# POWR001_BCR__LT3652.net
KiCad netlist of a schematic drawn in Altium Designer
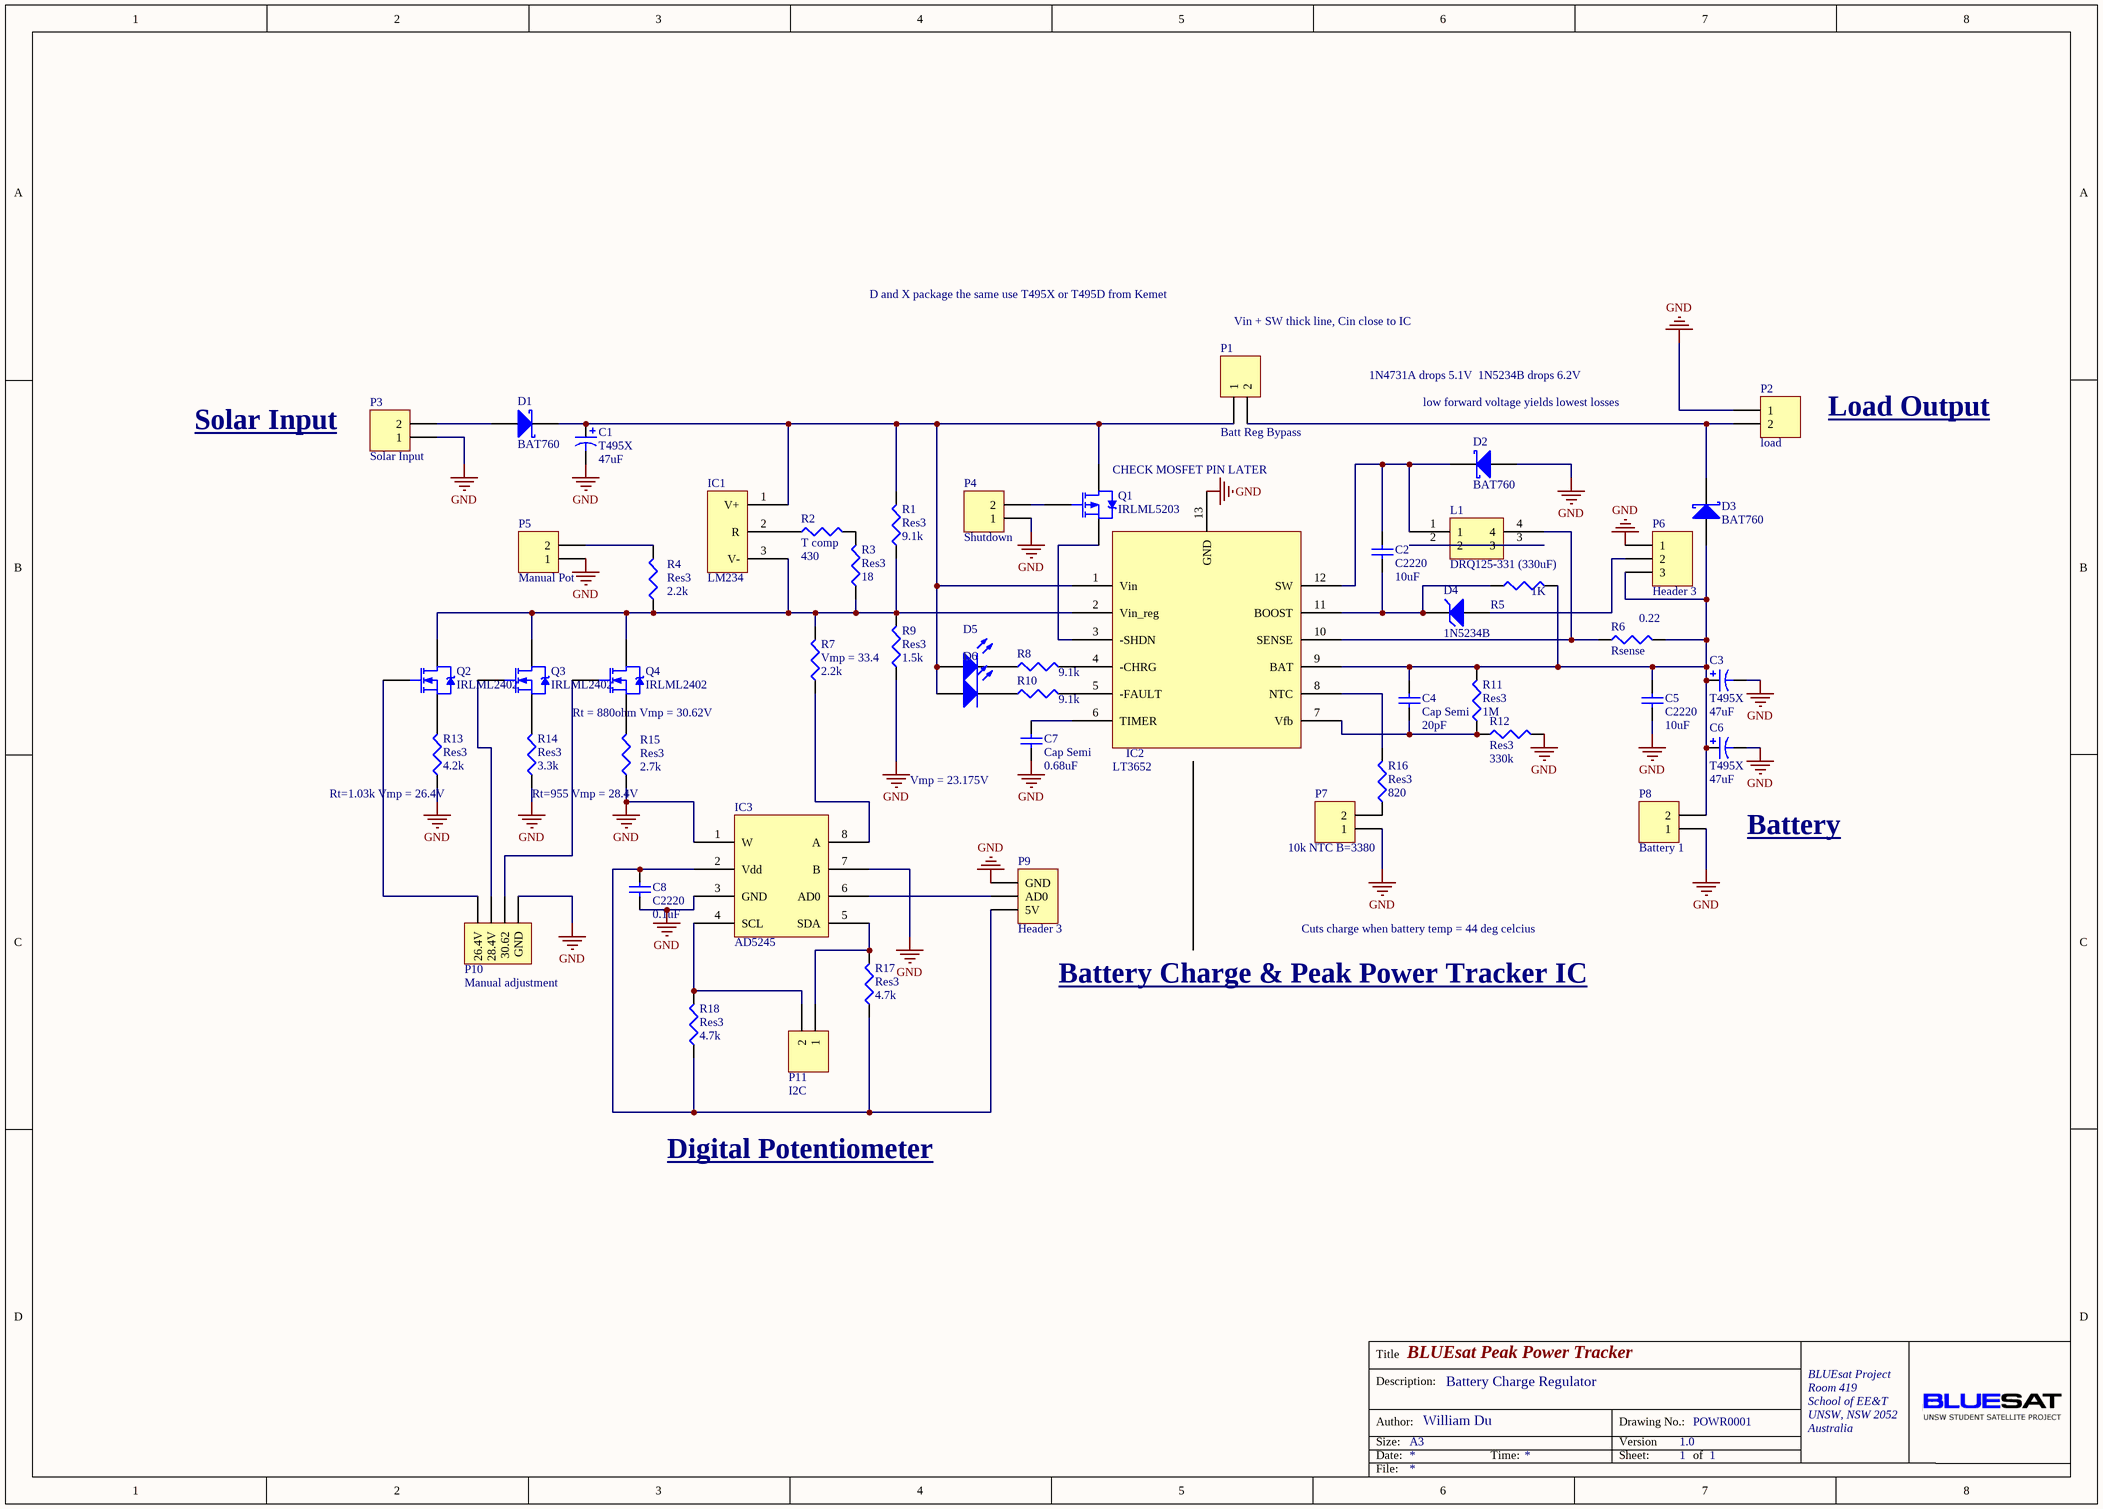
[diagram p0: POWR001_BCR_ LT3652.SchDoc]

(export (version "E")
  (design (tool "Eeschema 10.0.6"))
  (components
    (comp (ref "C1")
      (value "T495X")
      (footprint "X")
      (description "Solid Tantalum Chip Capacitor, Standard T495 Series - Low ESR, Surge Robust")
      (fields (field (name "ALTIUM_VALUE") "47uF") (field (name "PUBLISHER") "Altium Limited"))
      (libsource (lib "KEMET Chip Capacitor") (part "T495X"))
    )
    (comp (ref "C2")
      (value "C2220")
      (footprint "2220")
      (description "Ceramic Chip Capacitor - Standard")
      (fields (field (name "ALTIUM_VALUE") "10uF") (field (name "PUBLISHER") "Altium Limited"))
      (libsource (lib "KEMET Chip Capacitor") (part "C2220"))
    )
    (comp (ref "C3")
      (value "T495X")
      (footprint "X")
      (description "Solid Tantalum Chip Capacitor, Standard T495 Series - Low ESR, Surge Robust")
      (fields (field (name "ALTIUM_VALUE") "47uF") (field (name "PUBLISHER") "Altium Limited"))
      (libsource (lib "KEMET Chip Capacitor") (part "T495X"))
    )
    (comp (ref "C4")
      (value "Cap Semi")
      (footprint "CAPC3216L")
      (description "Capacitor (Semiconductor SIM Model)")
      (fields (field (name "ALTIUM_VALUE") "20pF") (field (name "PUBLISHER") "Altium Limited"))
      (libsource (lib "Miscellaneous Devices") (part "Cap Semi"))
    )
    (comp (ref "C5")
      (value "C2220")
      (footprint "2220")
      (description "Ceramic Chip Capacitor - Standard")
      (fields (field (name "ALTIUM_VALUE") "10uF") (field (name "PUBLISHER") "Altium Limited"))
      (libsource (lib "KEMET Chip Capacitor") (part "C2220"))
    )
    (comp (ref "C6")
      (value "T495X")
      (footprint "X")
      (description "Solid Tantalum Chip Capacitor, Standard T495 Series - Low ESR, Surge Robust")
      (fields (field (name "ALTIUM_VALUE") "47uF") (field (name "PUBLISHER") "Altium Limited"))
      (libsource (lib "KEMET Chip Capacitor") (part "T495X"))
    )
    (comp (ref "C7")
      (value "Cap Semi")
      (footprint "CAPC3216L")
      (description "Capacitor (Semiconductor SIM Model)")
      (fields (field (name "ALTIUM_VALUE") "0.68uF") (field (name "PUBLISHER") "Altium Limited"))
      (libsource (lib "Miscellaneous Devices") (part "Cap Semi"))
    )
    (comp (ref "C8")
      (value "C2220")
      (footprint "KEMET Electronics Footprints:2220")
      (description "Ceramic Chip Capacitor - Standard")
      (fields (field (name "ALTIUM_VALUE") "0.1uF") (field (name "PUBLISHER") "Altium Limited"))
      (libsource (lib "KEMET Chip Capacitor") (part "C2220"))
    )
    (comp (ref "D1")
      (value "BAT760")
      (footprint "SOD323")
      (description "Schottky Diode")
      (fields (field (name "PUBLISHER") "Altium Limited"))
      (libsource (lib "Miscellaneous Devices") (part "D Schottky"))
    )
    (comp (ref "D2")
      (value "BAT760")
      (footprint "LT3652:SOD323")
      (description "Schottky Diode")
      (fields (field (name "PUBLISHER") "Altium Limited"))
      (libsource (lib "Miscellaneous Devices") (part "D Schottky"))
    )
    (comp (ref "D3")
      (value "BAT760")
      (footprint "LT3652:SOD323")
      (description "Schottky Diode")
      (fields (field (name "PUBLISHER") "Altium Limited"))
      (libsource (lib "Miscellaneous Devices") (part "D Schottky"))
    )
    (comp (ref "D4")
      (value "1N5234B")
      (footprint "DO-35")
      (description "Half Watt Zener")
      (fields (field (name "PUBLISHER") "Altium Limited"))
      (libsource (lib "FSC Discrete Diode") (part "1N5234B"))
    )
    (comp (ref "D5")
      (value "~")
      (footprint "DSO-C2/D5.6")
      (description "Typical BLUE SiC LED")
      (fields (field (name "PUBLISHER") "Altium Limited"))
      (libsource (lib "Miscellaneous Devices") (part "LED3"))
    )
    (comp (ref "D6")
      (value "~")
      (footprint "DSO-C2/D5.6")
      (description "Typical BLUE SiC LED")
      (fields (field (name "PUBLISHER") "Altium Limited"))
      (libsource (lib "Miscellaneous Devices") (part "LED3"))
    )
    (comp (ref "IC1")
      (value "LM234")
      (footprint "Miscellaneous Connectors:HDR1X3")
      (libsource (lib "LT3652") (part "LM234"))
    )
    (comp (ref "IC2") (value "LT3652") (footprint "MSOP12") (libsource (lib "LT3652") (part "LT3652")))
    (comp (ref "IC3") (value "AD5245") (footprint "SOT23-8") (libsource (lib "LT3652") (part "AD5245")))
    (comp (ref "L1")
      (value "DRQ125-331 (330uF)")
      (footprint "DRQ125")
      (libsource (lib "LT3652") (part "DRQ125-331"))
    )
    (comp (ref "P1")
      (value "Batt Reg Bypass")
      (footprint "HDR1X2")
      (description "Header, 2-Pin")
      (fields (field (name "PUBLISHER") "Altium Limited"))
      (libsource (lib "") (part "Header 2_1"))
    )
    (comp (ref "P2")
      (value "load")
      (footprint "HDR1X2")
      (description "Header, 2-Pin")
      (fields (field (name "PUBLISHER") "Altium Limited"))
      (libsource (lib "") (part "Header 2_3"))
    )
    (comp (ref "P3")
      (value "Solar Input")
      (footprint "HDR1X2")
      (description "Header, 2-Pin")
      (fields (field (name "PUBLISHER") "Altium Limited"))
      (libsource (lib "Miscellaneous Connectors") (part "Header 2"))
    )
    (comp (ref "P4")
      (value "Shutdown")
      (footprint "HDR1X2")
      (description "Header, 2-Pin")
      (fields (field (name "PUBLISHER") "Altium Limited"))
      (libsource (lib "Miscellaneous Connectors") (part "Header 2"))
    )
    (comp (ref "P5")
      (value "Manual Pot")
      (footprint "HDR1X2")
      (description "Header, 2-Pin")
      (fields (field (name "PUBLISHER") "Altium Limited"))
      (libsource (lib "Miscellaneous Connectors") (part "Header 2"))
    )
    (comp (ref "P6")
      (value "Header 3")
      (footprint "HDR1X3")
      (description "Header, 3-Pin")
      (fields (field (name "PUBLISHER") "Altium Limited"))
      (libsource (lib "Miscellaneous Connectors") (part "Header 3"))
    )
    (comp (ref "P7")
      (value "10k NTC B=3380")
      (footprint "HDR1X2")
      (description "Header, 2-Pin")
      (fields (field (name "PUBLISHER") "Altium Limited"))
      (libsource (lib "Miscellaneous Connectors") (part "Header 2"))
    )
    (comp (ref "P8")
      (value "Battery 1")
      (footprint "HDR1X2")
      (description "Header, 2-Pin")
      (fields (field (name "PUBLISHER") "Altium Limited"))
      (libsource (lib "Miscellaneous Connectors") (part "Header 2"))
    )
    (comp (ref "P9")
      (value "Header 3")
      (footprint "HDR1X3")
      (description "Header, 3-Pin")
      (fields (field (name "PUBLISHER") "Altium Limited"))
      (libsource (lib "Miscellaneous Connectors") (part "Header 3"))
    )
    (comp (ref "P10")
      (value "Manual adjustment")
      (footprint "HDR1X4")
      (description "Header, 4-Pin")
      (fields (field (name "PUBLISHER") "Altium Limited"))
      (libsource (lib "Miscellaneous Connectors") (part "Header 4"))
    )
    (comp (ref "P11")
      (value "I2C")
      (footprint "HDR1X2")
      (description "Header, 2-Pin")
      (fields (field (name "PUBLISHER") "Altium Limited"))
      (libsource (lib "") (part "Header 2_2"))
    )
    (comp (ref "Q1")
      (value "IRLML5203")
      (footprint "International Rectifier Footprints:SOT-23")
      (description "HEXFET Power MOSFET 9103511")
      (fields (field (name "PUBLISHER") "Altium Limited"))
      (libsource (lib "IR Discrete MOSFET - Power") (part "IRLML5103"))
    )
    (comp (ref "Q2")
      (value "IRLML2402")
      (footprint "International Rectifier Footprints:SOT-23")
      (description "HEXFET Power MOSFET")
      (fields (field (name "PUBLISHER") "Altium Limited"))
      (libsource (lib "IR Discrete MOSFET - Power") (part "IRLML2402"))
    )
    (comp (ref "Q3")
      (value "IRLML2402")
      (footprint "International Rectifier Footprints:SOT-23")
      (description "HEXFET Power MOSFET")
      (fields (field (name "PUBLISHER") "Altium Limited"))
      (libsource (lib "IR Discrete MOSFET - Power") (part "IRLML2402"))
    )
    (comp (ref "Q4")
      (value "IRLML2402")
      (footprint "International Rectifier Footprints:SOT-23")
      (description "HEXFET Power MOSFET")
      (fields (field (name "PUBLISHER") "Altium Limited"))
      (libsource (lib "IR Discrete MOSFET - Power") (part "IRLML2402"))
    )
    (comp (ref "R1")
      (value "Res3")
      (footprint "RESC1608L")
      (description "Resistor")
      (fields (field (name "ALTIUM_VALUE") "9.1k") (field (name "PUBLISHER") "Altium Limited"))
      (libsource (lib "Miscellaneous Devices") (part "Res3"))
    )
    (comp (ref "R2")
      (value "T comp")
      (footprint "RESC1608L")
      (description "Resistor")
      (fields (field (name "ALTIUM_VALUE") "430") (field (name "PUBLISHER") "Altium Limited"))
      (libsource (lib "Miscellaneous Devices") (part "Res3"))
    )
    (comp (ref "R3")
      (value "Res3")
      (footprint "RESC1608L")
      (description "Resistor")
      (fields (field (name "ALTIUM_VALUE") "18") (field (name "PUBLISHER") "Altium Limited"))
      (libsource (lib "Miscellaneous Devices") (part "Res3"))
    )
    (comp (ref "R4")
      (value "Res3")
      (footprint "RESC1608L")
      (description "Resistor")
      (fields (field (name "ALTIUM_VALUE") "2.2k") (field (name "PUBLISHER") "Altium Limited"))
      (libsource (lib "Miscellaneous Devices") (part "Res3"))
    )
    (comp (ref "R5")
      (value "1K")
      (footprint "RESC1608L")
      (description "Resistor")
      (fields (field (name "PUBLISHER") "Altium Limited"))
      (libsource (lib "Miscellaneous Devices") (part "Res3"))
    )
    (comp (ref "R6")
      (value "Rsense")
      (footprint "RESC1608L")
      (description "Resistor")
      (fields (field (name "ALTIUM_VALUE") "0.22") (field (name "PUBLISHER") "Altium Limited"))
      (libsource (lib "Miscellaneous Devices") (part "Res3"))
    )
    (comp (ref "R7")
      (value "Vmp = 33.4")
      (footprint "RESC1608L")
      (description "Resistor")
      (fields (field (name "ALTIUM_VALUE") "2.2k") (field (name "PUBLISHER") "Altium Limited"))
      (libsource (lib "Miscellaneous Devices") (part "Res3"))
    )
    (comp (ref "R8")
      (value "9.1k")
      (footprint "RESC1608L")
      (description "Resistor")
      (fields (field (name "PUBLISHER") "Altium Limited"))
      (libsource (lib "Miscellaneous Devices") (part "Res3"))
    )
    (comp (ref "R9")
      (value "Res3")
      (footprint "RESC1608L")
      (description "Resistor")
      (fields (field (name "ALTIUM_VALUE") "1.5k") (field (name "PUBLISHER") "Altium Limited"))
      (libsource (lib "Miscellaneous Devices") (part "Res3"))
    )
    (comp (ref "R10")
      (value "9.1k")
      (footprint "RESC1608L")
      (description "Resistor")
      (fields (field (name "PUBLISHER") "Altium Limited"))
      (libsource (lib "Miscellaneous Devices") (part "Res3"))
    )
    (comp (ref "R11")
      (value "Res3")
      (footprint "RESC2012M")
      (description "Resistor")
      (fields (field (name "ALTIUM_VALUE") "1M") (field (name "PUBLISHER") "Altium Limited"))
      (libsource (lib "Miscellaneous Devices") (part "Res3"))
    )
    (comp (ref "R12")
      (value "Res3")
      (footprint "RESC1608L")
      (description "Resistor")
      (fields (field (name "ALTIUM_VALUE") "330k") (field (name "PUBLISHER") "Altium Limited"))
      (libsource (lib "Miscellaneous Devices") (part "Res3"))
    )
    (comp (ref "R13")
      (value "Res3")
      (footprint "RESC1608L")
      (description "Resistor")
      (fields (field (name "ALTIUM_VALUE") "4.2k") (field (name "PUBLISHER") "Altium Limited"))
      (libsource (lib "Miscellaneous Devices") (part "Res3"))
    )
    (comp (ref "R14")
      (value "Res3")
      (footprint "RESC1608L")
      (description "Resistor")
      (fields (field (name "ALTIUM_VALUE") "3.3k") (field (name "PUBLISHER") "Altium Limited"))
      (libsource (lib "Miscellaneous Devices") (part "Res3"))
    )
    (comp (ref "R15")
      (value "Res3")
      (footprint "RESC1608L")
      (description "Resistor")
      (fields (field (name "ALTIUM_VALUE") "2.7k") (field (name "PUBLISHER") "Altium Limited"))
      (libsource (lib "Miscellaneous Devices") (part "Res3"))
    )
    (comp (ref "R16")
      (value "Res3")
      (footprint "RESC1608L")
      (description "Resistor")
      (fields (field (name "ALTIUM_VALUE") "820") (field (name "PUBLISHER") "Altium Limited"))
      (libsource (lib "Miscellaneous Devices") (part "Res3"))
    )
    (comp (ref "R17")
      (value "Res3")
      (footprint "RESC1608L")
      (description "Resistor")
      (fields (field (name "ALTIUM_VALUE") "4.7k") (field (name "PUBLISHER") "Altium Limited"))
      (libsource (lib "Miscellaneous Devices") (part "Res3"))
    )
    (comp (ref "R18")
      (value "Res3")
      (footprint "RESC1608L")
      (description "Resistor")
      (fields (field (name "ALTIUM_VALUE") "4.7k") (field (name "PUBLISHER") "Altium Limited"))
      (libsource (lib "Miscellaneous Devices") (part "Res3"))
    )
  )
  (nets
    (net (code "1") (name "GND") (class "Default")
      (node (ref "C1") (pin "2") (pinfunction "2_2") (pintype "passive"))
      (node (ref "C3") (pin "2") (pinfunction "2_2") (pintype "passive"))
      (node (ref "C5") (pin "1") (pinfunction "1_1") (pintype "passive"))
      (node (ref "C6") (pin "2") (pinfunction "2_2") (pintype "passive"))
      (node (ref "C7") (pin "1") (pinfunction "1_1") (pintype "passive"))
      (node (ref "C8") (pin "1") (pinfunction "1_1") (pintype "passive"))
      (node (ref "D2") (pin "1") (pinfunction "A_1") (pintype "passive"))
      (node (ref "IC2") (pin "13") (pinfunction "GND_13") (pintype "passive"))
      (node (ref "IC3") (pin "1") (pinfunction "W_1") (pintype "passive"))
      (node (ref "IC3") (pin "3") (pinfunction "GND_3") (pintype "passive"))
      (node (ref "IC3") (pin "7") (pinfunction "B_7") (pintype "passive"))
      (node (ref "P10") (pin "1") (pinfunction "GND_1") (pintype "passive"))
      (node (ref "P2") (pin "1") (pinfunction "1_1") (pintype "passive"))
      (node (ref "P3") (pin "1") (pinfunction "1_1") (pintype "passive"))
      (node (ref "P4") (pin "1") (pinfunction "1_1") (pintype "passive"))
      (node (ref "P5") (pin "1") (pinfunction "1_1") (pintype "passive"))
      (node (ref "P6") (pin "1") (pinfunction "GND_1") (pintype "passive"))
      (node (ref "P7") (pin "1") (pinfunction "1_1") (pintype "passive"))
      (node (ref "P8") (pin "1") (pinfunction "1_1") (pintype "passive"))
      (node (ref "P9") (pin "1") (pinfunction "GND_1") (pintype "passive"))
      (node (ref "R12") (pin "2") (pinfunction "2_2") (pintype "passive"))
      (node (ref "R13") (pin "1") (pinfunction "1_1") (pintype "passive"))
      (node (ref "R14") (pin "1") (pinfunction "1_1") (pintype "passive"))
      (node (ref "R15") (pin "1") (pinfunction "1_1") (pintype "passive"))
      (node (ref "R9") (pin "1") (pinfunction "1_1") (pintype "passive"))
    )
    (net (code "2") (name "Net-(D1-A)") (class "Default")
      (node (ref "D1") (pin "1") (pinfunction "A_1") (pintype "passive"))
      (node (ref "P3") (pin "2") (pinfunction "2_2") (pintype "passive"))
    )
    (net (code "3") (name "Net-(D1-K)") (class "Default")
      (node (ref "C1") (pin "1") (pinfunction "1_1") (pintype "passive"))
      (node (ref "D1") (pin "2") (pinfunction "K_2") (pintype "passive"))
      (node (ref "D5") (pin "1") (pinfunction "A_1") (pintype "passive"))
      (node (ref "D6") (pin "1") (pinfunction "A_1") (pintype "passive"))
      (node (ref "IC1") (pin "1") (pinfunction "V+_1") (pintype "passive"))
      (node (ref "IC2") (pin "1") (pinfunction "Vin_1") (pintype "passive"))
      (node (ref "P1") (pin "1") (pinfunction "1_1") (pintype "passive"))
      (node (ref "Q1") (pin "3") (pinfunction "D_3") (pintype "passive"))
      (node (ref "R1") (pin "2") (pinfunction "2_2") (pintype "passive"))
    )
    (net (code "4") (name "Net-(D2-K)") (class "Default")
      (node (ref "C2") (pin "2") (pinfunction "2_2") (pintype "passive"))
      (node (ref "D2") (pin "2") (pinfunction "K_2") (pintype "passive"))
      (node (ref "IC2") (pin "12") (pinfunction "SW_12") (pintype "passive"))
      (node (ref "L1") (pin "1") (pinfunction "1_1") (pintype "passive"))
    )
    (net (code "5") (name "Net-(D3-A)") (class "Default")
      (node (ref "C3") (pin "1") (pinfunction "1_1") (pintype "passive"))
      (node (ref "C4") (pin "2") (pinfunction "2_2") (pintype "passive"))
      (node (ref "C5") (pin "2") (pinfunction "2_2") (pintype "passive"))
      (node (ref "C6") (pin "1") (pinfunction "1_1") (pintype "passive"))
      (node (ref "D3") (pin "1") (pinfunction "A_1") (pintype "passive"))
      (node (ref "IC2") (pin "9") (pinfunction "BAT_9") (pintype "passive"))
      (node (ref "P6") (pin "3") (pinfunction "5V_3") (pintype "passive"))
      (node (ref "P8") (pin "2") (pinfunction "2_2") (pintype "passive"))
      (node (ref "R11") (pin "2") (pinfunction "2_2") (pintype "passive"))
      (node (ref "R5") (pin "2") (pinfunction "2_2") (pintype "passive"))
      (node (ref "R6") (pin "2") (pinfunction "2_2") (pintype "passive"))
    )
    (net (code "6") (name "Net-(D3-K)") (class "Default")
      (node (ref "D3") (pin "2") (pinfunction "K_2") (pintype "passive"))
      (node (ref "P1") (pin "2") (pinfunction "2_2") (pintype "passive"))
      (node (ref "P2") (pin "2") (pinfunction "2_2") (pintype "passive"))
    )
    (net (code "7") (name "Net-(D4-A)") (class "Default")
      (node (ref "D4") (pin "1") (pinfunction "A_1") (pintype "passive"))
      (node (ref "P6") (pin "2") (pinfunction "AD0_2") (pintype "passive"))
    )
    (net (code "8") (name "Net-(D4-K)") (class "Default")
      (node (ref "C2") (pin "1") (pinfunction "1_1") (pintype "passive"))
      (node (ref "D4") (pin "2") (pinfunction "K_2") (pintype "passive"))
      (node (ref "IC2") (pin "11") (pinfunction "BOOST_11") (pintype "passive"))
      (node (ref "R5") (pin "1") (pinfunction "1_1") (pintype "passive"))
    )
    (net (code "9") (name "Net-(D5-K)") (class "Default")
      (node (ref "D5") (pin "2") (pinfunction "K_2") (pintype "passive"))
      (node (ref "R8") (pin "1") (pinfunction "1_1") (pintype "passive"))
    )
    (net (code "10") (name "Net-(D6-K)") (class "Default")
      (node (ref "D6") (pin "2") (pinfunction "K_2") (pintype "passive"))
      (node (ref "R10") (pin "1") (pinfunction "1_1") (pintype "passive"))
    )
    (net (code "11") (name "Net-(IC1-R)") (class "Default")
      (node (ref "IC1") (pin "2") (pinfunction "R_2") (pintype "passive"))
      (node (ref "R2") (pin "1") (pinfunction "1_1") (pintype "passive"))
    )
    (net (code "12") (name "Net-(IC1-V-)") (class "Default")
      (node (ref "IC1") (pin "3") (pinfunction "V-_3") (pintype "passive"))
      (node (ref "IC2") (pin "2") (pinfunction "Vin_reg_2") (pintype "passive"))
      (node (ref "Q2") (pin "3") (pinfunction "D_3") (pintype "passive"))
      (node (ref "Q3") (pin "3") (pinfunction "D_3") (pintype "passive"))
      (node (ref "Q4") (pin "3") (pinfunction "D_3") (pintype "passive"))
      (node (ref "R1") (pin "1") (pinfunction "1_1") (pintype "passive"))
      (node (ref "R3") (pin "1") (pinfunction "1_1") (pintype "passive"))
      (node (ref "R4") (pin "1") (pinfunction "1_1") (pintype "passive"))
      (node (ref "R7") (pin "2") (pinfunction "2_2") (pintype "passive"))
      (node (ref "R9") (pin "2") (pinfunction "2_2") (pintype "passive"))
    )
    (net (code "13") (name "Net-(IC2--CHRG)") (class "Default")
      (node (ref "IC2") (pin "4") (pinfunction "-CHRG_4") (pintype "passive"))
      (node (ref "R8") (pin "2") (pinfunction "2_2") (pintype "passive"))
    )
    (net (code "14") (name "Net-(IC2--FAULT)") (class "Default")
      (node (ref "IC2") (pin "5") (pinfunction "-FAULT_5") (pintype "passive"))
      (node (ref "R10") (pin "2") (pinfunction "2_2") (pintype "passive"))
    )
    (net (code "15") (name "Net-(IC2--SHDN)") (class "Default")
      (node (ref "IC2") (pin "3") (pinfunction "-SHDN_3") (pintype "passive"))
      (node (ref "Q1") (pin "2") (pinfunction "S_2") (pintype "passive"))
    )
    (net (code "16") (name "Net-(IC2-NTC)") (class "Default")
      (node (ref "IC2") (pin "8") (pinfunction "NTC_8") (pintype "passive"))
      (node (ref "R16") (pin "2") (pinfunction "2_2") (pintype "passive"))
    )
    (net (code "17") (name "Net-(IC2-SENSE)") (class "Default")
      (node (ref "IC2") (pin "10") (pinfunction "SENSE_10") (pintype "passive"))
      (node (ref "L1") (pin "4") (pinfunction "4_4") (pintype "passive"))
      (node (ref "R6") (pin "1") (pinfunction "1_1") (pintype "passive"))
    )
    (net (code "18") (name "Net-(IC2-TIMER)") (class "Default")
      (node (ref "C7") (pin "2") (pinfunction "2_2") (pintype "passive"))
      (node (ref "IC2") (pin "6") (pinfunction "TIMER_6") (pintype "passive"))
    )
    (net (code "19") (name "Net-(IC2-Vfb)") (class "Default")
      (node (ref "C4") (pin "1") (pinfunction "1_1") (pintype "passive"))
      (node (ref "IC2") (pin "7") (pinfunction "Vfb_7") (pintype "passive"))
      (node (ref "R11") (pin "1") (pinfunction "1_1") (pintype "passive"))
      (node (ref "R12") (pin "1") (pinfunction "1_1") (pintype "passive"))
    )
    (net (code "20") (name "Net-(IC3-A)") (class "Default")
      (node (ref "IC3") (pin "8") (pinfunction "A_8") (pintype "passive"))
      (node (ref "R7") (pin "1") (pinfunction "1_1") (pintype "passive"))
    )
    (net (code "21") (name "Net-(IC3-AD0)") (class "Default")
      (node (ref "IC3") (pin "6") (pinfunction "AD0_6") (pintype "passive"))
      (node (ref "P9") (pin "2") (pinfunction "AD0_2") (pintype "passive"))
    )
    (net (code "22") (name "Net-(IC3-SCL)") (class "Default")
      (node (ref "IC3") (pin "4") (pinfunction "SCL_4") (pintype "passive"))
      (node (ref "P11") (pin "2") (pinfunction "2_2") (pintype "passive"))
      (node (ref "R18") (pin "2") (pinfunction "2_2") (pintype "passive"))
    )
    (net (code "23") (name "Net-(IC3-SDA)") (class "Default")
      (node (ref "IC3") (pin "5") (pinfunction "SDA_5") (pintype "passive"))
      (node (ref "P11") (pin "1") (pinfunction "1_1") (pintype "passive"))
      (node (ref "R17") (pin "2") (pinfunction "2_2") (pintype "passive"))
    )
    (net (code "24") (name "Net-(IC3-Vdd)") (class "Default")
      (node (ref "C8") (pin "2") (pinfunction "2_2") (pintype "passive"))
      (node (ref "IC3") (pin "2") (pinfunction "Vdd_2") (pintype "passive"))
      (node (ref "P9") (pin "3") (pinfunction "5V_3") (pintype "passive"))
      (node (ref "R17") (pin "1") (pinfunction "1_1") (pintype "passive"))
      (node (ref "R18") (pin "1") (pinfunction "1_1") (pintype "passive"))
    )
    (net (code "25") (name "Net-(L1-Pad2)") (class "Default")
      (node (ref "L1") (pin "2") (pinfunction "2_2") (pintype "passive"))
      (node (ref "L1") (pin "3") (pinfunction "3_3") (pintype "passive"))
    )
    (net (code "26") (name "Net-(P5-Pad2)") (class "Default")
      (node (ref "P5") (pin "2") (pinfunction "2_2") (pintype "passive"))
      (node (ref "R4") (pin "2") (pinfunction "2_2") (pintype "passive"))
    )
    (net (code "27") (name "Net-(P7-Pad2)") (class "Default")
      (node (ref "P7") (pin "2") (pinfunction "2_2") (pintype "passive"))
      (node (ref "R16") (pin "1") (pinfunction "1_1") (pintype "passive"))
    )
    (net (code "28") (name "Net-(P10-26.4V)") (class "Default")
      (node (ref "P10") (pin "4") (pinfunction "26.4V_4") (pintype "passive"))
      (node (ref "Q2") (pin "1") (pinfunction "G_1") (pintype "passive"))
    )
    (net (code "29") (name "Net-(P10-28.4V)") (class "Default")
      (node (ref "P10") (pin "3") (pinfunction "28.4V_3") (pintype "passive"))
      (node (ref "Q3") (pin "1") (pinfunction "G_1") (pintype "passive"))
    )
    (net (code "30") (name "Net-(P10-30.62)") (class "Default")
      (node (ref "P10") (pin "2") (pinfunction "30.62_2") (pintype "passive"))
      (node (ref "Q4") (pin "1") (pinfunction "G_1") (pintype "passive"))
    )
    (net (code "31") (name "Net-(Q1-G)") (class "Default")
      (node (ref "P4") (pin "2") (pinfunction "2_2") (pintype "passive"))
      (node (ref "Q1") (pin "1") (pinfunction "G_1") (pintype "passive"))
    )
    (net (code "32") (name "Net-(Q2-S)") (class "Default")
      (node (ref "Q2") (pin "2") (pinfunction "S_2") (pintype "passive"))
      (node (ref "R13") (pin "2") (pinfunction "2_2") (pintype "passive"))
    )
    (net (code "33") (name "Net-(Q3-S)") (class "Default")
      (node (ref "Q3") (pin "2") (pinfunction "S_2") (pintype "passive"))
      (node (ref "R14") (pin "2") (pinfunction "2_2") (pintype "passive"))
    )
    (net (code "34") (name "Net-(Q4-S)") (class "Default")
      (node (ref "Q4") (pin "2") (pinfunction "S_2") (pintype "passive"))
      (node (ref "R15") (pin "2") (pinfunction "2_2") (pintype "passive"))
    )
    (net (code "35") (name "Net-(R2-Pad2)") (class "Default")
      (node (ref "R2") (pin "2") (pinfunction "2_2") (pintype "passive"))
      (node (ref "R3") (pin "2") (pinfunction "2_2") (pintype "passive"))
    )
  )
)
